# Buck_Converter.net
KiCad netlist of a schematic drawn in Altium Designer
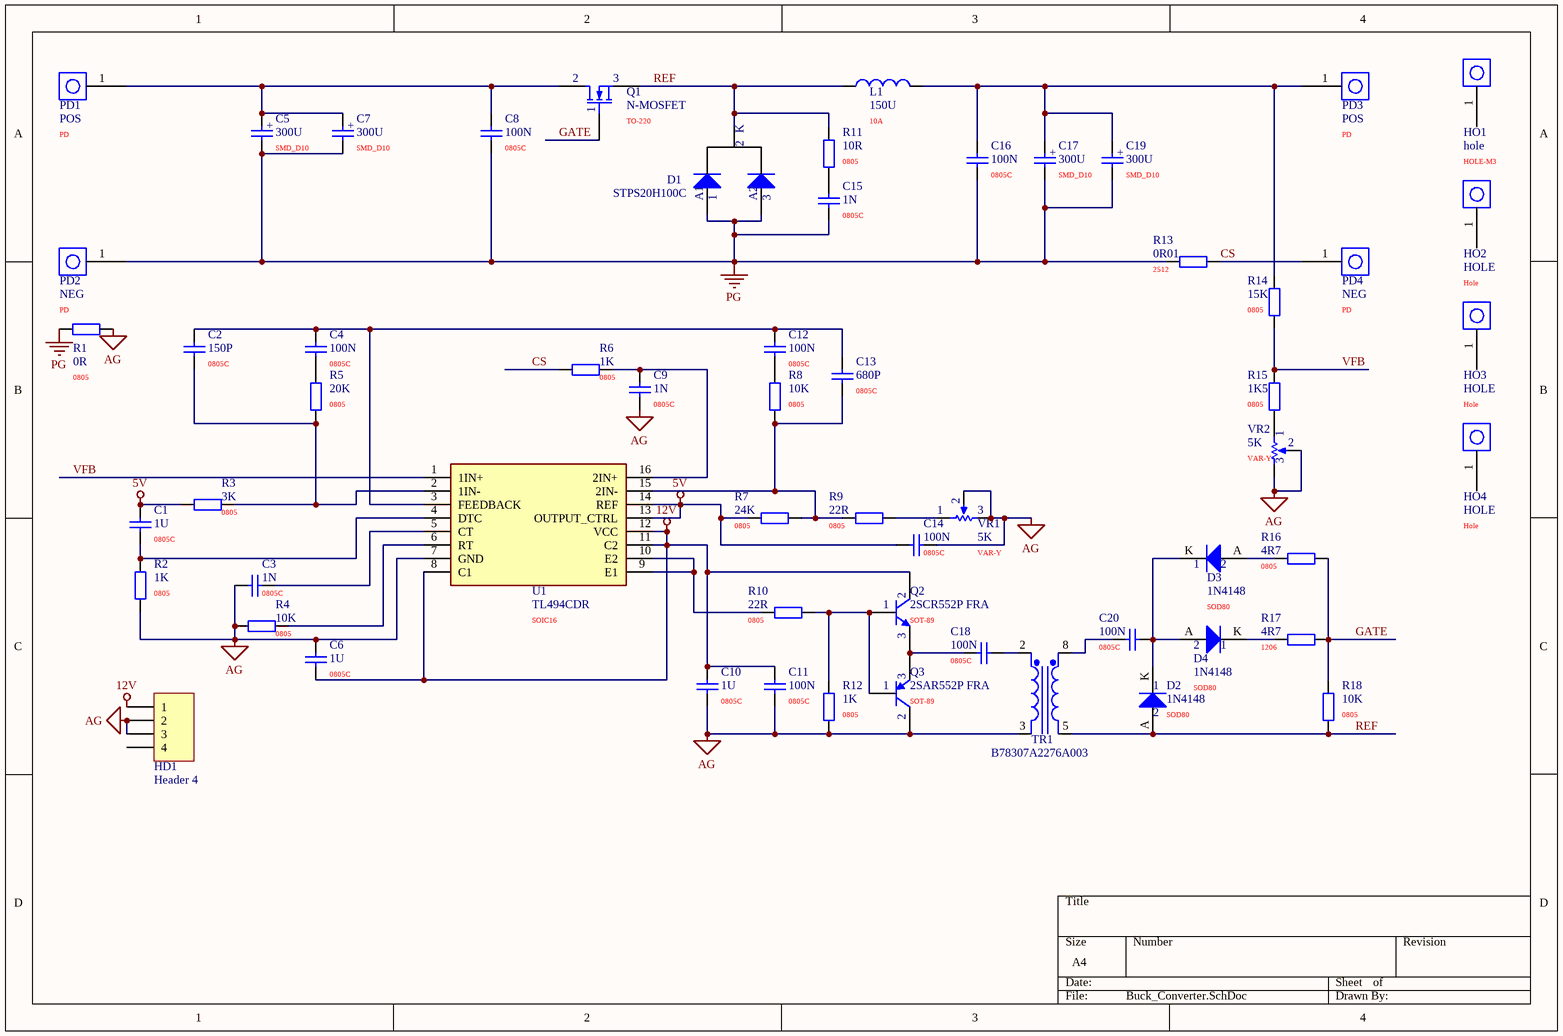
[diagram p0: Buck_Converter.SchDoc]

(export (version "E")
  (design (tool "Eeschema 10.0.6"))
  (components
    (comp (ref "C1")
      (value "1uF")
      (footprint "Capacitors_SMD_0805")
      (description "SMD_0805")
      (libsource (lib "Buck_Converter_Component") (part "C1"))
    )
    (comp (ref "C2")
      (value "150pF")
      (footprint "Capacitors_SMD_0805")
      (description "SMD_0805")
      (libsource (lib "Buck_Converter_Component") (part "C2"))
    )
    (comp (ref "C3")
      (value "1nF")
      (footprint "Capacitors_SMD_0805")
      (description "SMD_0805")
      (libsource (lib "Buck_Converter_Component") (part "C3"))
    )
    (comp (ref "C4")
      (value "100nF")
      (footprint "Capacitors_SMD_0805")
      (description "SMD_0805")
      (libsource (lib "Buck_Converter_Component") (part "C4"))
    )
    (comp (ref "C5")
      (value "330uf")
      (footprint "Capacitors_SMD_D10")
      (description "SMD_D10")
      (libsource (lib "Buck_Converter_Component") (part "C5"))
    )
    (comp (ref "C6")
      (value "1uF")
      (footprint "Capacitors_SMD_0805")
      (description "SMD_0805")
      (libsource (lib "Buck_Converter_Component") (part "C6"))
    )
    (comp (ref "C7")
      (value "330uf")
      (footprint "Capacitors_SMD_D10")
      (description "SMD_D10")
      (libsource (lib "Buck_Converter_Component") (part "C7"))
    )
    (comp (ref "C8")
      (value "100nF")
      (footprint "Capacitors_SMD_0805")
      (description "SMD_0805")
      (libsource (lib "Buck_Converter_Component") (part "C8"))
    )
    (comp (ref "C9")
      (value "1nF")
      (footprint "Capacitors_SMD_0805")
      (description "SMD_0805")
      (libsource (lib "Buck_Converter_Component") (part "C9"))
    )
    (comp (ref "C10")
      (value "1uF")
      (footprint "Capacitors_SMD_0805")
      (description "SMD_0805")
      (libsource (lib "Buck_Converter_Component") (part "C10"))
    )
    (comp (ref "C11")
      (value "100nF")
      (footprint "Capacitors_SMD_0805")
      (description "SMD_0805")
      (libsource (lib "Buck_Converter_Component") (part "C11"))
    )
    (comp (ref "C12")
      (value "100nF")
      (footprint "Capacitors_SMD_0805")
      (description "SMD_0805")
      (libsource (lib "Buck_Converter_Component") (part "C12"))
    )
    (comp (ref "C13")
      (value "680pF")
      (footprint "Capacitors_SMD_0805")
      (description "SMD_0805")
      (libsource (lib "Buck_Converter_Component") (part "C13"))
    )
    (comp (ref "C14")
      (value "100nF")
      (footprint "Capacitors_SMD_0805")
      (description "SMD_0805")
      (libsource (lib "Buck_Converter_Component") (part "C14"))
    )
    (comp (ref "C15")
      (value "1nF")
      (footprint "Capacitors_SMD_0805")
      (description "SMD_0805")
      (libsource (lib "Buck_Converter_Component") (part "C15"))
    )
    (comp (ref "C16")
      (value "100nF")
      (footprint "Capacitors_SMD_0805")
      (description "SMD_0805")
      (libsource (lib "Buck_Converter_Component") (part "C16"))
    )
    (comp (ref "C17")
      (value "330uF")
      (footprint "Capacitors_SMD_D10")
      (description "SMD_D10")
      (libsource (lib "Buck_Converter_Component") (part "C17"))
    )
    (comp (ref "C18")
      (value "100nF")
      (footprint "Capacitors_SMD_0805")
      (description "SMD_0805")
      (libsource (lib "Buck_Converter_Component") (part "C18"))
    )
    (comp (ref "C19")
      (value "330uF")
      (footprint "Capacitors_SMD_D10")
      (description "SMD_D10")
      (libsource (lib "Buck_Converter_Component") (part "C19"))
    )
    (comp (ref "C20")
      (value "100nF")
      (footprint "Capacitors_SMD_0805")
      (description "SMD_0805")
      (libsource (lib "Buck_Converter_Component") (part "C20"))
    )
    (comp (ref "D1")
      (value "STPS20H100C")
      (footprint "TO-220_Diode")
      (description "Schottky")
      (libsource (lib "Buck_Converter_Component") (part "D1"))
    )
    (comp (ref "D2")
      (value "1N4148")
      (footprint "1N4148")
      (description "Diode")
      (libsource (lib "Buck_Converter_Component") (part "D2"))
    )
    (comp (ref "D3")
      (value "1N4148")
      (footprint "1N4148")
      (description "Diode")
      (libsource (lib "Buck_Converter_Component") (part "D3"))
    )
    (comp (ref "D4")
      (value "1N4148")
      (footprint "1N4148")
      (description "Diode")
      (libsource (lib "Buck_Converter_Component") (part "D4"))
    )
    (comp (ref "HD1")
      (value "Header 4")
      (footprint "HDR1X4")
      (description "Header, 4-Pin")
      (fields (field (name "PUBLISHER") "Altium Limited"))
      (libsource (lib "Miscellaneous Connectors") (part "Header 4"))
    )
    (comp (ref "HO1")
      (value "HOLE")
      (footprint "Hole")
      (libsource (lib "Buck_Converter_Component") (part "HO1"))
    )
    (comp (ref "HO2")
      (value "HOLE")
      (footprint "Hole")
      (libsource (lib "Buck_Converter_Component") (part "HO2"))
    )
    (comp (ref "HO3")
      (value "HOLE")
      (footprint "Hole")
      (libsource (lib "Buck_Converter_Component") (part "HO3"))
    )
    (comp (ref "HO4")
      (value "HOLE")
      (footprint "Hole")
      (libsource (lib "Buck_Converter_Component") (part "HO4"))
    )
    (comp (ref "L1")
      (value "Inductor")
      (footprint "Inductor")
      (libsource (lib "Buck_Converter_Component") (part "L1"))
    )
    (comp (ref "PD1")
      (value "Terminal")
      (footprint "Terminal")
      (libsource (lib "Buck_Converter_Component") (part "PD1"))
    )
    (comp (ref "PD2")
      (value "Terminal")
      (footprint "Terminal")
      (libsource (lib "Buck_Converter_Component") (part "PD2"))
    )
    (comp (ref "PD3")
      (value "Terminal")
      (footprint "Terminal")
      (libsource (lib "Buck_Converter_Component") (part "PD3"))
    )
    (comp (ref "PD4")
      (value "Terminal")
      (footprint "Terminal")
      (libsource (lib "Buck_Converter_Component") (part "PD4"))
    )
    (comp (ref "Q1")
      (value "N-MOSFET")
      (footprint "TO-220)N-MOSFET")
      (libsource (lib "Buck_Converter_Component") (part "Q1"))
    )
    (comp (ref "Q2")
      (value "2SCR552P")
      (footprint "2SCR552P")
      (description "NPN-BJT")
      (libsource (lib "Buck_Converter_Component") (part "Q2"))
    )
    (comp (ref "Q3")
      (value "2SAR552P")
      (footprint "2SAR552P")
      (description "PNP-BJT")
      (libsource (lib "Buck_Converter_Component") (part "Q3"))
    )
    (comp (ref "R1")
      (value "0R")
      (footprint "RESISTOR_SMD_0805")
      (description "SMD_0805")
      (libsource (lib "Buck_Converter_Component") (part "R1"))
    )
    (comp (ref "R2")
      (value "1K")
      (footprint "RESISTOR_SMD_0805")
      (description "SMD_0805")
      (libsource (lib "Buck_Converter_Component") (part "R2"))
    )
    (comp (ref "R3")
      (value "3K")
      (footprint "RESISTOR_SMD_0805")
      (description "SMD_0805")
      (libsource (lib "Buck_Converter_Component") (part "R3"))
    )
    (comp (ref "R4")
      (value "10K")
      (footprint "RESISTOR_SMD_0805")
      (description "SMD_0805")
      (libsource (lib "Buck_Converter_Component") (part "R4"))
    )
    (comp (ref "R5")
      (value "20K")
      (footprint "RESISTOR_SMD_0805")
      (description "SMD_0805")
      (libsource (lib "Buck_Converter_Component") (part "R5"))
    )
    (comp (ref "R6")
      (value "1K")
      (footprint "RESISTOR_SMD_0805")
      (description "SMD_0805")
      (libsource (lib "Buck_Converter_Component") (part "R6"))
    )
    (comp (ref "R7")
      (value "24K")
      (footprint "RESISTOR_SMD_0805")
      (description "SMD_0805")
      (libsource (lib "Buck_Converter_Component") (part "R7"))
    )
    (comp (ref "R8")
      (value "10K")
      (footprint "RESISTOR_SMD_0805")
      (description "SMD_0805")
      (libsource (lib "Buck_Converter_Component") (part "R8"))
    )
    (comp (ref "R9")
      (value "22R")
      (footprint "RESISTOR_SMD_0805")
      (description "SMD_0805")
      (libsource (lib "Buck_Converter_Component") (part "R9"))
    )
    (comp (ref "R10")
      (value "22R")
      (footprint "RESISTOR_SMD_0805")
      (description "SMD_0805")
      (libsource (lib "Buck_Converter_Component") (part "R10"))
    )
    (comp (ref "R11")
      (value "10R")
      (footprint "RESISTOR_SMD_0805")
      (description "SMD_0805")
      (libsource (lib "Buck_Converter_Component") (part "R11"))
    )
    (comp (ref "R12")
      (value "1K")
      (footprint "RESISTOR_SMD_0805")
      (description "SMD_0805")
      (libsource (lib "Buck_Converter_Component") (part "R12"))
    )
    (comp (ref "R13")
      (value "0R01")
      (footprint "RESISTOR_SMD_2512")
      (description "SMD_2512")
      (libsource (lib "Buck_Converter_Component") (part "R13"))
    )
    (comp (ref "R14")
      (value "15K")
      (footprint "RESISTOR_SMD_0805")
      (description "SMD_0805")
      (libsource (lib "Buck_Converter_Component") (part "R14"))
    )
    (comp (ref "R15")
      (value "1K5")
      (footprint "RESISTOR_SMD_0805")
      (description "SMD_0805")
      (libsource (lib "Buck_Converter_Component") (part "R15"))
    )
    (comp (ref "R16")
      (value "4R7")
      (footprint "RESISTOR_SMD_0805")
      (description "SMD_0805")
      (libsource (lib "Buck_Converter_Component") (part "R16"))
    )
    (comp (ref "R17")
      (value "4R7")
      (footprint "RESISTOR_SMD_1206")
      (description "SMD_1206")
      (libsource (lib "Buck_Converter_Component") (part "R17"))
    )
    (comp (ref "R18")
      (value "10K")
      (footprint "RESISTOR_SMD_0805")
      (description "SMD_0805")
      (libsource (lib "Buck_Converter_Component") (part "R18"))
    )
    (comp (ref "TL494CDR")
      (value "TL494CDR")
      (footprint "TL494CDR")
      (description "PWM_controller")
      (libsource (lib "Buck_Converter_Component") (part "TL494CDR"))
    )
    (comp (ref "TR1")
      (value "B78307A2276A003")
      (footprint "B78307A2276A003")
      (description "SMDTransformers")
      (libsource (lib "Buck_Converter_Component") (part "TR1"))
    )
    (comp (ref "VR1")
      (value "5K")
      (footprint "Baoter_3296")
      (description "Baoter_3296")
      (libsource (lib "Buck_Converter_Component") (part "VR1"))
    )
    (comp (ref "VR2")
      (value "5K")
      (footprint "Baoter_3296")
      (description "Baoter_3296")
      (libsource (lib "Buck_Converter_Component") (part "VR2"))
    )
  )
  (nets
    (net (code "1") (name "/CS") (class "Default")
      (node (ref "PD4") (pin "1") (pinfunction "3_1") (pintype "passive"))
      (node (ref "R13") (pin "2") (pinfunction "2_2") (pintype "passive"))
      (node (ref "R6") (pin "1") (pinfunction "1_1") (pintype "passive"))
    )
    (net (code "2") (name "/GATE") (class "Default")
      (node (ref "Q1") (pin "1") (pinfunction "G_1") (pintype "passive"))
      (node (ref "R16") (pin "2") (pinfunction "2_2") (pintype "passive"))
      (node (ref "R17") (pin "2") (pinfunction "2_2") (pintype "passive"))
      (node (ref "R18") (pin "2") (pinfunction "2_2") (pintype "passive"))
    )
    (net (code "3") (name "/REF") (class "Default")
      (node (ref "D1") (pin "K") (pinfunction "K_K") (pintype "passive"))
      (node (ref "D2") (pin "A") (pinfunction "A_A") (pintype "passive"))
      (node (ref "L1") (pin "1") (pinfunction "1_1") (pintype "passive"))
      (node (ref "Q1") (pin "3") (pinfunction "S_3") (pintype "passive"))
      (node (ref "R11") (pin "2") (pinfunction "2_2") (pintype "passive"))
      (node (ref "R18") (pin "1") (pinfunction "1_1") (pintype "passive"))
      (node (ref "TR1") (pin "5") (pinfunction "Sec-_5") (pintype "passive"))
    )
    (net (code "4") (name "/VFB") (class "Default")
      (node (ref "R14") (pin "1") (pinfunction "1_1") (pintype "passive"))
      (node (ref "R15") (pin "2") (pinfunction "2_2") (pintype "passive"))
      (node (ref "TL494CDR") (pin "1") (pinfunction "1IN+_1") (pintype "passive"))
    )
    (net (code "5") (name "5V") (class "Default")
      (node (ref "C1") (pin "2") (pinfunction "2_2") (pintype "passive"))
      (node (ref "C14") (pin "1") (pinfunction "1_1") (pintype "passive"))
      (node (ref "R3") (pin "1") (pinfunction "1_1") (pintype "passive"))
      (node (ref "R7") (pin "1") (pinfunction "1_1") (pintype "passive"))
      (node (ref "TL494CDR") (pin "13") (pinfunction "OUTPUT_CTRL_13") (pintype "passive"))
      (node (ref "TL494CDR") (pin "14") (pinfunction "REF_14") (pintype "passive"))
    )
    (net (code "6") (name "12V") (class "Default")
      (node (ref "C10") (pin "2") (pinfunction "2_2") (pintype "passive"))
      (node (ref "C11") (pin "2") (pinfunction "2_2") (pintype "passive"))
      (node (ref "C6") (pin "2") (pinfunction "2_2") (pintype "passive"))
      (node (ref "HD1") (pin "1") (pinfunction "1_1") (pintype "passive"))
      (node (ref "Q2") (pin "2") (pinfunction "C_2") (pintype "passive"))
      (node (ref "TL494CDR") (pin "11") (pinfunction "C2_11") (pintype "passive"))
      (node (ref "TL494CDR") (pin "12") (pinfunction "VCC_12") (pintype "passive"))
      (node (ref "TL494CDR") (pin "8") (pinfunction "C1_8") (pintype "passive"))
    )
    (net (code "7") (name "AG") (class "Default")
      (node (ref "C10") (pin "1") (pinfunction "1_1") (pintype "passive"))
      (node (ref "C11") (pin "1") (pinfunction "1_1") (pintype "passive"))
      (node (ref "C14") (pin "2") (pinfunction "2_2") (pintype "passive"))
      (node (ref "C3") (pin "1") (pinfunction "1_1") (pintype "passive"))
      (node (ref "C6") (pin "1") (pinfunction "1_1") (pintype "passive"))
      (node (ref "C9") (pin "1") (pinfunction "1_1") (pintype "passive"))
      (node (ref "HD1") (pin "2") (pinfunction "2_2") (pintype "passive"))
      (node (ref "HD1") (pin "3") (pinfunction "3_3") (pintype "passive"))
      (node (ref "Q3") (pin "2") (pinfunction "C_2") (pintype "passive"))
      (node (ref "R1") (pin "2") (pinfunction "2_2") (pintype "passive"))
      (node (ref "R12") (pin "1") (pinfunction "1_1") (pintype "passive"))
      (node (ref "R2") (pin "1") (pinfunction "1_1") (pintype "passive"))
      (node (ref "R4") (pin "1") (pinfunction "1_1") (pintype "passive"))
      (node (ref "TL494CDR") (pin "7") (pinfunction "GND_7") (pintype "passive"))
      (node (ref "TR1") (pin "3") (pinfunction "Pri-_3") (pintype "passive"))
      (node (ref "VR1") (pin "2") (pinfunction "TAP_2") (pintype "passive"))
      (node (ref "VR1") (pin "3") (pinfunction "TOP_3") (pintype "passive"))
      (node (ref "VR2") (pin "2") (pinfunction "TAP_2") (pintype "passive"))
      (node (ref "VR2") (pin "3") (pinfunction "TOP_3") (pintype "passive"))
    )
    (net (code "8") (name "Net-(C4-Pad1)") (class "Default")
      (node (ref "C4") (pin "1") (pinfunction "1_1") (pintype "passive"))
      (node (ref "R5") (pin "1") (pinfunction "1_1") (pintype "passive"))
    )
    (net (code "9") (name "Net-(C12-Pad1)") (class "Default")
      (node (ref "C12") (pin "1") (pinfunction "1_1") (pintype "passive"))
      (node (ref "R8") (pin "2") (pinfunction "2_2") (pintype "passive"))
    )
    (net (code "10") (name "Net-(C15-Pad1)") (class "Default")
      (node (ref "C15") (pin "1") (pinfunction "1_1") (pintype "passive"))
      (node (ref "R11") (pin "1") (pinfunction "1_1") (pintype "passive"))
    )
    (net (code "11") (name "Net-(C20-Pad2)") (class "Default")
      (node (ref "C20") (pin "2") (pinfunction "2_2") (pintype "passive"))
      (node (ref "D2") (pin "K") (pinfunction "K_K") (pintype "passive"))
      (node (ref "D3") (pin "K") (pinfunction "K_K") (pintype "passive"))
      (node (ref "D4") (pin "A") (pinfunction "A_A") (pintype "passive"))
    )
    (net (code "12") (name "Net-(D3-PadA)") (class "Default")
      (node (ref "D3") (pin "A") (pinfunction "A_A") (pintype "passive"))
      (node (ref "R16") (pin "1") (pinfunction "1_1") (pintype "passive"))
    )
    (net (code "13") (name "Net-(D4-PadK)") (class "Default")
      (node (ref "D4") (pin "K") (pinfunction "K_K") (pintype "passive"))
      (node (ref "R17") (pin "1") (pinfunction "1_1") (pintype "passive"))
    )
    (net (code "14") (name "Net-(PD1-3)") (class "Default")
      (node (ref "C5") (pin "1") (pinfunction "1_1") (pintype "passive"))
      (node (ref "C7") (pin "1") (pinfunction "1_1") (pintype "passive"))
      (node (ref "C8") (pin "1") (pinfunction "1_1") (pintype "passive"))
      (node (ref "PD1") (pin "1") (pinfunction "3_1") (pintype "passive"))
      (node (ref "Q1") (pin "2") (pinfunction "D_2") (pintype "passive"))
    )
    (net (code "15") (name "Net-(PD3-3)") (class "Default")
      (node (ref "C16") (pin "2") (pinfunction "2_2") (pintype "passive"))
      (node (ref "C17") (pin "1") (pinfunction "1_1") (pintype "passive"))
      (node (ref "C19") (pin "1") (pinfunction "1_1") (pintype "passive"))
      (node (ref "L1") (pin "2") (pinfunction "2_2") (pintype "passive"))
      (node (ref "PD3") (pin "1") (pinfunction "3_1") (pintype "passive"))
      (node (ref "R14") (pin "2") (pinfunction "2_2") (pintype "passive"))
    )
    (net (code "16") (name "Net-(Q2-B)") (class "Default")
      (node (ref "Q2") (pin "1") (pinfunction "B_1") (pintype "passive"))
      (node (ref "Q3") (pin "1") (pinfunction "B_1") (pintype "passive"))
      (node (ref "R10") (pin "2") (pinfunction "2_2") (pintype "passive"))
      (node (ref "R12") (pin "2") (pinfunction "2_2") (pintype "passive"))
    )
    (net (code "17") (name "Net-(Q2-E)") (class "Default")
      (node (ref "C18") (pin "1") (pinfunction "1_1") (pintype "passive"))
      (node (ref "Q2") (pin "3") (pinfunction "E_3") (pintype "passive"))
      (node (ref "Q3") (pin "3") (pinfunction "E_3") (pintype "passive"))
    )
    (net (code "18") (name "Net-(TL494CDR-1IN-)") (class "Default")
      (node (ref "C2") (pin "1") (pinfunction "1_1") (pintype "passive"))
      (node (ref "R3") (pin "2") (pinfunction "2_2") (pintype "passive"))
      (node (ref "R5") (pin "2") (pinfunction "2_2") (pintype "passive"))
      (node (ref "TL494CDR") (pin "2") (pinfunction "1IN-_2") (pintype "passive"))
    )
    (net (code "19") (name "Net-(TL494CDR-2IN+)") (class "Default")
      (node (ref "C9") (pin "2") (pinfunction "2_2") (pintype "passive"))
      (node (ref "R6") (pin "2") (pinfunction "2_2") (pintype "passive"))
      (node (ref "TL494CDR") (pin "16") (pinfunction "2IN+_16") (pintype "passive"))
    )
    (net (code "20") (name "Net-(TL494CDR-2IN-)") (class "Default")
      (node (ref "C13") (pin "2") (pinfunction "2_2") (pintype "passive"))
      (node (ref "R7") (pin "2") (pinfunction "2_2") (pintype "passive"))
      (node (ref "R8") (pin "1") (pinfunction "1_1") (pintype "passive"))
      (node (ref "R9") (pin "1") (pinfunction "1_1") (pintype "passive"))
      (node (ref "TL494CDR") (pin "15") (pinfunction "2IN-_15") (pintype "passive"))
    )
    (net (code "21") (name "Net-(TL494CDR-CT)") (class "Default")
      (node (ref "C3") (pin "2") (pinfunction "2_2") (pintype "passive"))
      (node (ref "TL494CDR") (pin "5") (pinfunction "CT_5") (pintype "passive"))
    )
    (net (code "22") (name "Net-(TL494CDR-DTC)") (class "Default")
      (node (ref "C1") (pin "1") (pinfunction "1_1") (pintype "passive"))
      (node (ref "R2") (pin "2") (pinfunction "2_2") (pintype "passive"))
      (node (ref "TL494CDR") (pin "4") (pinfunction "DTC_4") (pintype "passive"))
    )
    (net (code "23") (name "Net-(TL494CDR-E1)") (class "Default")
      (node (ref "R10") (pin "1") (pinfunction "1_1") (pintype "passive"))
      (node (ref "TL494CDR") (pin "10") (pinfunction "E2_10") (pintype "passive"))
      (node (ref "TL494CDR") (pin "9") (pinfunction "E1_9") (pintype "passive"))
    )
    (net (code "24") (name "Net-(TL494CDR-FEEDBACK)") (class "Default")
      (node (ref "C12") (pin "2") (pinfunction "2_2") (pintype "passive"))
      (node (ref "C13") (pin "1") (pinfunction "1_1") (pintype "passive"))
      (node (ref "C2") (pin "2") (pinfunction "2_2") (pintype "passive"))
      (node (ref "C4") (pin "2") (pinfunction "2_2") (pintype "passive"))
      (node (ref "TL494CDR") (pin "3") (pinfunction "FEEDBACK_3") (pintype "passive"))
    )
    (net (code "25") (name "Net-(TL494CDR-RT)") (class "Default")
      (node (ref "R4") (pin "2") (pinfunction "2_2") (pintype "passive"))
      (node (ref "TL494CDR") (pin "6") (pinfunction "RT_6") (pintype "passive"))
    )
    (net (code "26") (name "Net-(TR1-Pri+)") (class "Default")
      (node (ref "C18") (pin "2") (pinfunction "2_2") (pintype "passive"))
      (node (ref "TR1") (pin "2") (pinfunction "Pri+_2") (pintype "passive"))
    )
    (net (code "27") (name "Net-(TR1-Sec+)") (class "Default")
      (node (ref "C20") (pin "1") (pinfunction "1_1") (pintype "passive"))
      (node (ref "TR1") (pin "8") (pinfunction "Sec+_8") (pintype "passive"))
    )
    (net (code "28") (name "Net-(VR1-BOT)") (class "Default")
      (node (ref "R9") (pin "2") (pinfunction "2_2") (pintype "passive"))
      (node (ref "VR1") (pin "1") (pinfunction "BOT_1") (pintype "passive"))
    )
    (net (code "29") (name "Net-(VR2-BOT)") (class "Default")
      (node (ref "R15") (pin "1") (pinfunction "1_1") (pintype "passive"))
      (node (ref "VR2") (pin "1") (pinfunction "BOT_1") (pintype "passive"))
    )
    (net (code "30") (name "PG") (class "Default")
      (node (ref "C15") (pin "2") (pinfunction "2_2") (pintype "passive"))
      (node (ref "C16") (pin "1") (pinfunction "1_1") (pintype "passive"))
      (node (ref "C17") (pin "2") (pinfunction "2_2") (pintype "passive"))
      (node (ref "C19") (pin "2") (pinfunction "2_2") (pintype "passive"))
      (node (ref "C5") (pin "2") (pinfunction "2_2") (pintype "passive"))
      (node (ref "C7") (pin "2") (pinfunction "2_2") (pintype "passive"))
      (node (ref "C8") (pin "2") (pinfunction "2_2") (pintype "passive"))
      (node (ref "D1") (pin "A1") (pinfunction "A1_A1") (pintype "passive"))
      (node (ref "D1") (pin "A2") (pinfunction "A2_A2") (pintype "passive"))
      (node (ref "PD2") (pin "1") (pinfunction "3_1") (pintype "passive"))
      (node (ref "R1") (pin "1") (pinfunction "1_1") (pintype "passive"))
      (node (ref "R13") (pin "1") (pinfunction "1_1") (pintype "passive"))
    )
    (net (code "31") (name "unconnected-(HD1-Pad4)") (class "Default")
      (node (ref "HD1") (pin "4") (pinfunction "4_4") (pintype "passive"))
    )
    (net (code "32") (name "unconnected-(HO1-Pad1)") (class "Default")
      (node (ref "HO1") (pin "1") (pinfunction "1_1") (pintype "passive"))
    )
    (net (code "33") (name "unconnected-(HO2-Pad1)") (class "Default")
      (node (ref "HO2") (pin "1") (pinfunction "1_1") (pintype "passive"))
    )
    (net (code "34") (name "unconnected-(HO3-Pad1)") (class "Default")
      (node (ref "HO3") (pin "1") (pinfunction "1_1") (pintype "passive"))
    )
    (net (code "35") (name "unconnected-(HO4-Pad1)") (class "Default")
      (node (ref "HO4") (pin "1") (pinfunction "1_1") (pintype "passive"))
    )
  )
)
